# light_sensor_basic.net
KiCad netlist of a schematic drawn in EAGLE
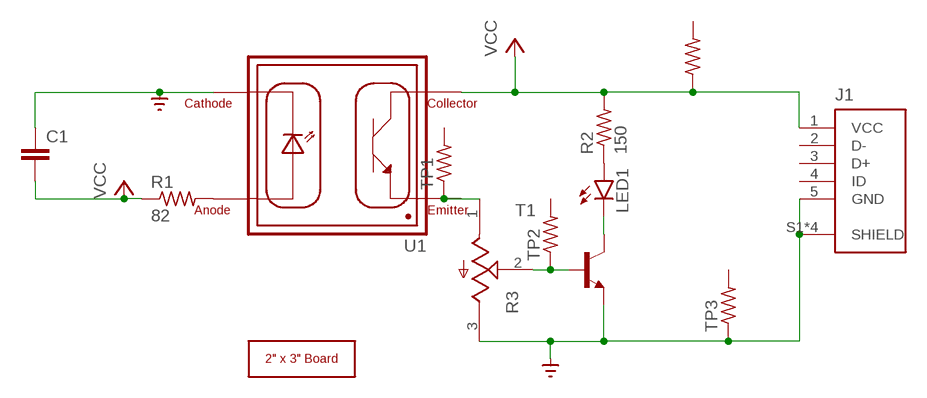
[diagram p0: schematic, sheet 1]

(export (version "E")
  (design (tool "Eeschema 10.0.6"))
  (components
    (comp (ref "C1")
      (value "0.1 uF")
      (footprint "eagle-import:C1206")
      (libsource (lib "eagle-import") (part "C-EUC1206"))
    )
    (comp (ref "J1")
      (value "UJ2-MIBH-G-SMT-TR")
      (footprint "eagle-import:CUI_UJ2-MIBH-G-SMT-TR")
      (fields (field (name "MANUFACTURER") "CUI"))
      (libsource (lib "eagle-import") (part "UJ2-MIBH-G-SMT-TR"))
    )
    (comp (ref "LED1")
      (value "LEDSML0805")
      (footprint "eagle-import:SML0805")
      (libsource (lib "eagle-import") (part "LEDSML0805"))
    )
    (comp (ref "R1")
      (value "82")
      (footprint "eagle-import:R0805")
      (libsource (lib "eagle-import") (part "R-US_R0805"))
    )
    (comp (ref "R2")
      (value "150")
      (footprint "eagle-import:R0805")
      (libsource (lib "eagle-import") (part "R-US_R0805"))
    )
    (comp (ref "R3")
      (value "TC33X-2-203E")
      (footprint "eagle-import:TRIM_TC33X-2-203E")
      (fields (field (name "DIGIKEY_PART_NUMBER") "TC33X-2-203ETR-ND") (field (name "MF") "Bourns"))
      (libsource (lib "eagle-import") (part "TC33X-2-203E"))
    )
    (comp (ref "T1")
      (value "-NPN-SOT23-EBC")
      (footprint "eagle-import:SOT23-EBC")
      (libsource (lib "eagle-import") (part "-NPN-SOT23-EBC"))
    )
    (comp (ref "TP1")
      (value "R-US_R1206")
      (footprint "eagle-import:R1206")
      (libsource (lib "eagle-import") (part "R-US_R1206"))
    )
    (comp (ref "TP2")
      (value "R-US_R1206")
      (footprint "eagle-import:R1206")
      (libsource (lib "eagle-import") (part "R-US_R1206"))
    )
    (comp (ref "TP3")
      (value "R-US_R1206")
      (footprint "eagle-import:R1206")
      (libsource (lib "eagle-import") (part "R-US_R1206"))
    )
    (comp (ref "TP4")
      (value "R-US_R1206")
      (footprint "eagle-import:R1206")
      (libsource (lib "eagle-import") (part "R-US_R1206"))
    )
    (comp (ref "U$1")
      (value "2X3_BOARD")
      (footprint "eagle-import:2X3_BOARD_V1")
      (libsource (lib "eagle-import") (part "2X3_BOARD"))
    )
    (comp (ref "U1")
      (value "VCNT2020")
      (footprint "eagle-import:XDCR_VCNT2020")
      (fields (field (name "DIGIKEY_PART_NUMBER") "VCNT2020TR-ND") (field (name "MF") "Vishay"))
      (libsource (lib "eagle-import") (part "VCNT2020"))
    )
  )
  (nets
    (net (code "1") (name "Net-(LED1-PadA)") (class "Default")
      (node (ref "LED1") (pin "A") (pinfunction "A_A") (pintype "passive"))
      (node (ref "R2") (pin "1") (pinfunction "1_1") (pintype "passive"))
    )
    (net (code "2") (name "Net-(LED1-PadC)") (class "Default")
      (node (ref "LED1") (pin "C") (pinfunction "C_C") (pintype "passive"))
      (node (ref "T1") (pin "C") (pinfunction "C_C") (pintype "passive"))
    )
    (net (code "3") (name "Net-(R3-CCW)") (class "Default")
      (node (ref "R3") (pin "1") (pinfunction "CCW_1") (pintype "passive"))
      (node (ref "TP1") (pin "1") (pinfunction "1_1") (pintype "passive"))
      (node (ref "U1") (pin "1") (pinfunction "EMITTER_1") (pintype "passive"))
    )
    (net (code "4") (name "Net-(R3-W)") (class "Default")
      (node (ref "R3") (pin "2") (pinfunction "W_2") (pintype "passive"))
      (node (ref "T1") (pin "B") (pinfunction "B_B") (pintype "passive"))
      (node (ref "TP2") (pin "1") (pinfunction "1_1") (pintype "passive"))
    )
    (net (code "5") (name "Net-(U1-ANODE)") (class "Default")
      (node (ref "R1") (pin "2") (pinfunction "2_2") (pintype "passive"))
      (node (ref "U1") (pin "3") (pinfunction "ANODE_3") (pintype "passive"))
    )
    (net (code "6") (name "SUPPLY_BRASTAN_GND_") (class "Default")
      (node (ref "C1") (pin "1") (pinfunction "1_1") (pintype "passive"))
      (node (ref "J1") (pin "5") (pinfunction "GND_5") (pintype "power_in"))
      (node (ref "J1") (pin "S1") (pinfunction "SHIELD_S1") (pintype "passive"))
      (node (ref "J1") (pin "S2") (pinfunction "SHIELD_S2") (pintype "passive"))
      (node (ref "J1") (pin "S3") (pinfunction "SHIELD_S3") (pintype "passive"))
      (node (ref "J1") (pin "S4") (pinfunction "SHIELD_S4") (pintype "passive"))
      (node (ref "R3") (pin "3") (pinfunction "CW_3") (pintype "passive"))
      (node (ref "T1") (pin "E") (pinfunction "E_E") (pintype "passive"))
      (node (ref "TP3") (pin "1") (pinfunction "1_1") (pintype "passive"))
      (node (ref "U1") (pin "4") (pinfunction "CATHODE_4") (pintype "passive"))
    )
    (net (code "7") (name "VCC") (class "Default")
      (node (ref "C1") (pin "2") (pinfunction "2_2") (pintype "passive"))
      (node (ref "J1") (pin "1") (pinfunction "VCC_1") (pintype "power_in"))
      (node (ref "R1") (pin "1") (pinfunction "1_1") (pintype "passive"))
      (node (ref "R2") (pin "2") (pinfunction "2_2") (pintype "passive"))
      (node (ref "TP4") (pin "1") (pinfunction "1_1") (pintype "passive"))
      (node (ref "U1") (pin "2") (pinfunction "COLLECTOR_2") (pintype "passive"))
    )
    (net (code "8") (name "unconnected-(J1-D+-Pad3)") (class "Default")
      (node (ref "J1") (pin "3") (pinfunction "D+_3") (pintype "bidirectional"))
    )
    (net (code "9") (name "unconnected-(J1-D--Pad2)") (class "Default")
      (node (ref "J1") (pin "2") (pinfunction "D-_2") (pintype "bidirectional"))
    )
    (net (code "10") (name "unconnected-(J1-ID-Pad4)") (class "Default")
      (node (ref "J1") (pin "4") (pinfunction "ID_4") (pintype "bidirectional"))
    )
    (net (code "11") (name "unconnected-(TP1-Pad2)") (class "Default")
      (node (ref "TP1") (pin "2") (pinfunction "2_2") (pintype "passive"))
    )
    (net (code "12") (name "unconnected-(TP2-Pad2)") (class "Default")
      (node (ref "TP2") (pin "2") (pinfunction "2_2") (pintype "passive"))
    )
    (net (code "13") (name "unconnected-(TP3-Pad2)") (class "Default")
      (node (ref "TP3") (pin "2") (pinfunction "2_2") (pintype "passive"))
    )
    (net (code "14") (name "unconnected-(TP4-Pad2)") (class "Default")
      (node (ref "TP4") (pin "2") (pinfunction "2_2") (pintype "passive"))
    )
  )
)
